# 14_-CURRENT_METER.net
KiCad netlist of a schematic drawn in Altium Designer
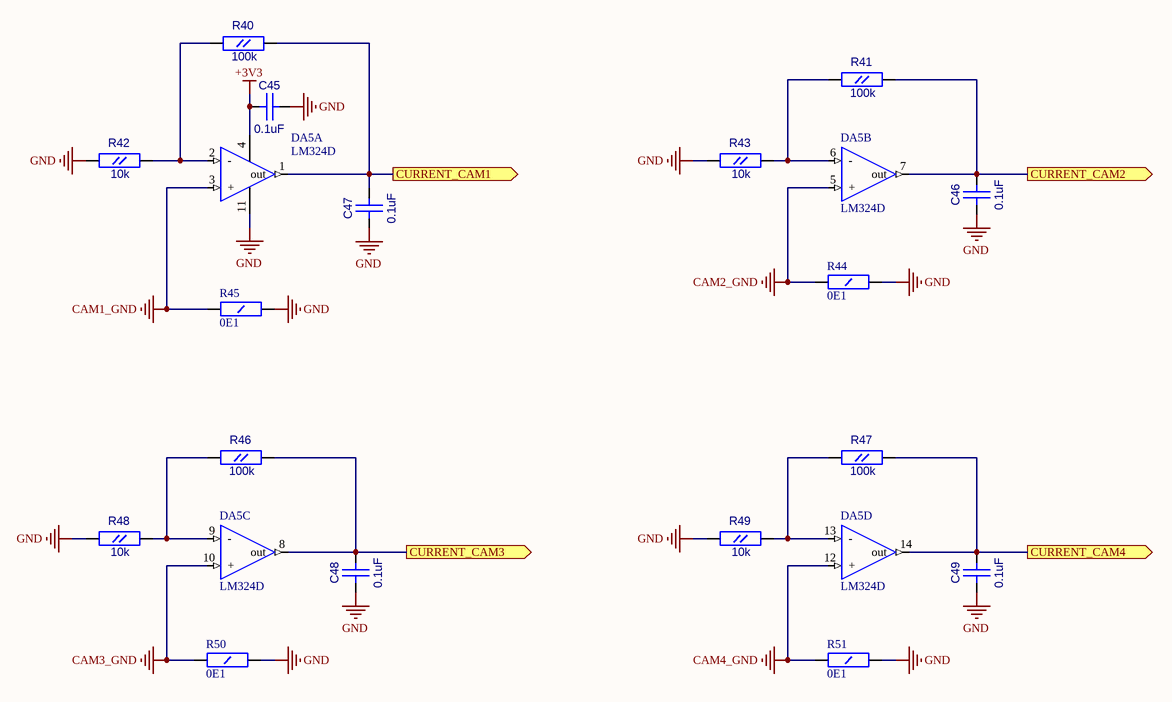
[diagram p0: [14]-CURRENT_METER.SchDoc]

(export (version "E")
  (design (tool "Eeschema 10.0.6"))
  (components
    (comp (ref "C45")
      (value "0.1uF")
      (footprint "CC0603")
      (description "CC0603")
      (libsource (lib "fizik_lib") (part "CC0603"))
    )
    (comp (ref "C46")
      (value "0.1uF")
      (footprint "CC0603")
      (description "CC0603")
      (libsource (lib "fizik_lib") (part "CC0603"))
    )
    (comp (ref "C47")
      (value "0.1uF")
      (footprint "CC0603")
      (description "CC0603")
      (libsource (lib "fizik_lib") (part "CC0603"))
    )
    (comp (ref "C48")
      (value "0.1uF")
      (footprint "CC0603")
      (description "CC0603")
      (libsource (lib "fizik_lib") (part "CC0603"))
    )
    (comp (ref "C49")
      (value "0.1uF")
      (footprint "CC0603")
      (description "CC0603")
      (libsource (lib "fizik_lib") (part "CC0603"))
    )
    (comp (ref "DA5") (value "LM324D") (footprint "SO14") (libsource (lib "fizik_lib") (part "LM324D")))
    (comp (ref "R40")
      (value "100k")
      (footprint "RC0603")
      (description "RC0603")
      (libsource (lib "fizik_lib") (part "RC0603"))
    )
    (comp (ref "R41")
      (value "100k")
      (footprint "RC0603")
      (description "RC0603")
      (libsource (lib "fizik_lib") (part "RC0603"))
    )
    (comp (ref "R42")
      (value "10k")
      (footprint "RC0603")
      (description "RC0603")
      (libsource (lib "fizik_lib") (part "RC0603"))
    )
    (comp (ref "R43")
      (value "10k")
      (footprint "RC0603")
      (description "RC0603")
      (libsource (lib "fizik_lib") (part "RC0603"))
    )
    (comp (ref "R44")
      (value "0E1")
      (footprint "R2512")
      (description "Resistor 2512 1W")
      (libsource (lib "fizik_lib") (part "RC2512"))
    )
    (comp (ref "R45")
      (value "0E1")
      (footprint "R2512")
      (description "Resistor 2512 1W")
      (libsource (lib "fizik_lib") (part "RC2512"))
    )
    (comp (ref "R46")
      (value "100k")
      (footprint "RC0603")
      (description "RC0603")
      (libsource (lib "fizik_lib") (part "RC0603"))
    )
    (comp (ref "R47")
      (value "100k")
      (footprint "RC0603")
      (description "RC0603")
      (libsource (lib "fizik_lib") (part "RC0603"))
    )
    (comp (ref "R48")
      (value "10k")
      (footprint "RC0603")
      (description "RC0603")
      (libsource (lib "fizik_lib") (part "RC0603"))
    )
    (comp (ref "R49")
      (value "10k")
      (footprint "RC0603")
      (description "RC0603")
      (libsource (lib "fizik_lib") (part "RC0603"))
    )
    (comp (ref "R50")
      (value "0E1")
      (footprint "R2512")
      (description "Resistor 2512 1W")
      (libsource (lib "fizik_lib") (part "RC2512"))
    )
    (comp (ref "R51")
      (value "0E1")
      (footprint "R2512")
      (description "Resistor 2512 1W")
      (libsource (lib "fizik_lib") (part "RC2512"))
    )
  )
  (nets
    (net (code "1") (name "+3V3") (class "Default")
      (node (ref "C45") (pin "1") (pinfunction "A_1") (pintype "passive"))
      (node (ref "DA5") (pin "4") (pinfunction "V+_4") (pintype "passive"))
    )
    (net (code "2") (name "/CURRENT_CAM1") (class "Default")
      (node (ref "C47") (pin "2") (pinfunction "B_2") (pintype "passive"))
      (node (ref "DA5") (pin "1") (pinfunction "out_1") (pintype "output"))
      (node (ref "R40") (pin "2") (pinfunction "B_2") (pintype "passive"))
    )
    (net (code "3") (name "/CURRENT_CAM2") (class "Default")
      (node (ref "C46") (pin "2") (pinfunction "B_2") (pintype "passive"))
      (node (ref "DA5") (pin "7") (pinfunction "out_7") (pintype "output"))
      (node (ref "R41") (pin "2") (pinfunction "B_2") (pintype "passive"))
    )
    (net (code "4") (name "/CURRENT_CAM3") (class "Default")
      (node (ref "C48") (pin "2") (pinfunction "B_2") (pintype "passive"))
      (node (ref "DA5") (pin "8") (pinfunction "out_8") (pintype "output"))
      (node (ref "R46") (pin "2") (pinfunction "B_2") (pintype "passive"))
    )
    (net (code "5") (name "/CURRENT_CAM4") (class "Default")
      (node (ref "C49") (pin "2") (pinfunction "B_2") (pintype "passive"))
      (node (ref "DA5") (pin "14") (pinfunction "out_14") (pintype "output"))
      (node (ref "R47") (pin "2") (pinfunction "B_2") (pintype "passive"))
    )
    (net (code "6") (name "CAM1_GND") (class "Default")
      (node (ref "DA5") (pin "3") (pinfunction "+_3") (pintype "input"))
      (node (ref "R45") (pin "2") (pinfunction "B_2") (pintype "passive"))
    )
    (net (code "7") (name "CAM2_GND") (class "Default")
      (node (ref "DA5") (pin "5") (pinfunction "+_5") (pintype "input"))
      (node (ref "R44") (pin "2") (pinfunction "B_2") (pintype "passive"))
    )
    (net (code "8") (name "CAM3_GND") (class "Default")
      (node (ref "DA5") (pin "10") (pinfunction "+_10") (pintype "input"))
      (node (ref "R50") (pin "2") (pinfunction "B_2") (pintype "passive"))
    )
    (net (code "9") (name "CAM4_GND") (class "Default")
      (node (ref "DA5") (pin "12") (pinfunction "+_12") (pintype "input"))
      (node (ref "R51") (pin "2") (pinfunction "B_2") (pintype "passive"))
    )
    (net (code "10") (name "GND") (class "Default")
      (node (ref "C45") (pin "2") (pinfunction "B_2") (pintype "passive"))
      (node (ref "C46") (pin "1") (pinfunction "A_1") (pintype "passive"))
      (node (ref "C47") (pin "1") (pinfunction "A_1") (pintype "passive"))
      (node (ref "C48") (pin "1") (pinfunction "A_1") (pintype "passive"))
      (node (ref "C49") (pin "1") (pinfunction "A_1") (pintype "passive"))
      (node (ref "DA5") (pin "11") (pinfunction "V-_11") (pintype "passive"))
      (node (ref "R42") (pin "1") (pinfunction "A_1") (pintype "passive"))
      (node (ref "R43") (pin "1") (pinfunction "A_1") (pintype "passive"))
      (node (ref "R44") (pin "1") (pinfunction "A_1") (pintype "passive"))
      (node (ref "R45") (pin "1") (pinfunction "A_1") (pintype "passive"))
      (node (ref "R48") (pin "1") (pinfunction "A_1") (pintype "passive"))
      (node (ref "R49") (pin "1") (pinfunction "A_1") (pintype "passive"))
      (node (ref "R50") (pin "1") (pinfunction "A_1") (pintype "passive"))
      (node (ref "R51") (pin "1") (pinfunction "A_1") (pintype "passive"))
    )
    (net (code "11") (name "Net-(DA5A--)") (class "Default")
      (node (ref "DA5") (pin "2") (pinfunction "-_2") (pintype "input"))
      (node (ref "R40") (pin "1") (pinfunction "A_1") (pintype "passive"))
      (node (ref "R42") (pin "2") (pinfunction "B_2") (pintype "passive"))
    )
    (net (code "12") (name "Net-(DA5B--)") (class "Default")
      (node (ref "DA5") (pin "6") (pinfunction "-_6") (pintype "input"))
      (node (ref "R41") (pin "1") (pinfunction "A_1") (pintype "passive"))
      (node (ref "R43") (pin "2") (pinfunction "B_2") (pintype "passive"))
    )
    (net (code "13") (name "Net-(DA5C--)") (class "Default")
      (node (ref "DA5") (pin "9") (pinfunction "-_9") (pintype "input"))
      (node (ref "R46") (pin "1") (pinfunction "A_1") (pintype "passive"))
      (node (ref "R48") (pin "2") (pinfunction "B_2") (pintype "passive"))
    )
    (net (code "14") (name "Net-(DA5D--)") (class "Default")
      (node (ref "DA5") (pin "13") (pinfunction "-_13") (pintype "input"))
      (node (ref "R47") (pin "1") (pinfunction "A_1") (pintype "passive"))
      (node (ref "R49") (pin "2") (pinfunction "B_2") (pintype "passive"))
    )
  )
)
